# design.net
KiCad netlist of a schematic drawn in Altium Designer
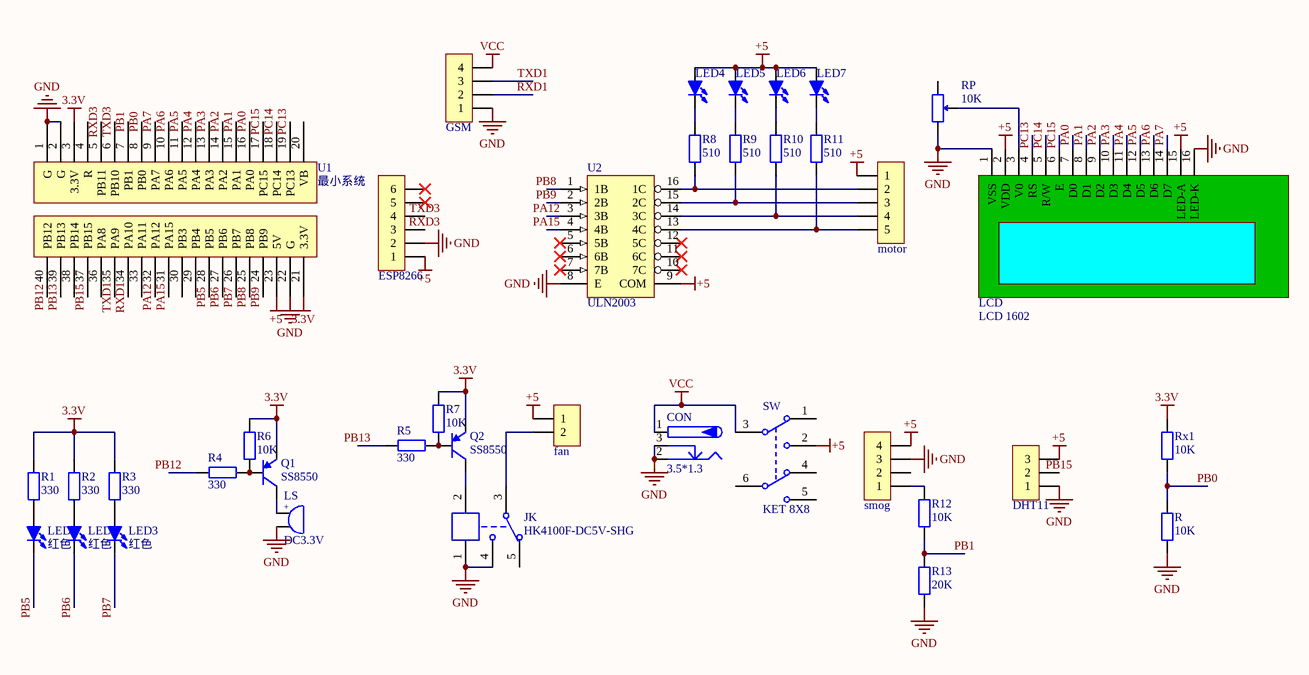
[diagram p0: 原理图.SchDoc]

(export (version "E")
  (design (tool "Eeschema 10.0.6"))
  (components
    (comp (ref "CON")
      (value "3.5*1.3")
      (footprint "DC-005")
      (description "低压电源接口")
      (fields (field (name "版权归属") "源创客"))
      (libsource (lib "4.1   - 接口类") (part "P-DC"))
    )
    (comp (ref "DHT11")
      (value "HDR-1X3")
      (footprint "HDR2.54-M-LI-3P")
      (description "3P接插件")
      (fields (field (name "版权归属") "源创客"))
      (libsource (lib "4.5   - 接插件-脚距2.54") (part "Header 3"))
    )
    (comp (ref "ESP8266")
      (value "HDR-1X6")
      (footprint "HDR2.54-M-LI-6P")
      (description "6P接插件")
      (fields (field (name "版权归属") "源创客"))
      (libsource (lib "4.5   - 接插件-脚距2.54") (part "Header 6"))
    )
    (comp (ref "fan")
      (value "HDR-1X2")
      (footprint "HDR2.54-LI-2P")
      (description "2P接插件")
      (fields (field (name "版权归属") "源创客"))
      (libsource (lib "4.5   - 接插件-脚距2.54") (part "Header 2"))
    )
    (comp (ref "GSM")
      (value "HDR-1X4")
      (footprint "HDR2.54-LI-4P")
      (description "4P接插件")
      (fields (field (name "版权归属") "源创客"))
      (libsource (lib "4.5   - 接插件-脚距2.54") (part "Header 4"))
    )
    (comp (ref "JK")
      (value "HK4100F-DC5V-SHG")
      (footprint "HK4100F")
      (description "一组转换")
      (fields (field (name "版权归属") "源创客"))
      (libsource (lib "7.1   - 继电器") (part "HK4100F"))
    )
    (comp (ref "LCD")
      (value "LCD 1602")
      (footprint "LCD-1602")
      (fields (field (name "版权归属") "源创客"))
      (libsource (lib "9.2   - 显示器件") (part "LCD 1602"))
    )
    (comp (ref "LED1")
      (value "红色")
      (footprint "LED 0805G")
      (description "贴片LED")
      (fields (field (name "版权归属") "源创客"))
      (libsource (lib "9.1   - LED") (part "LED-SMD"))
    )
    (comp (ref "LED2")
      (value "红色")
      (footprint "LED 0805G")
      (description "贴片LED")
      (fields (field (name "版权归属") "源创客"))
      (libsource (lib "9.1   - LED") (part "LED-SMD"))
    )
    (comp (ref "LED3")
      (value "红色")
      (footprint "LED 0805G")
      (description "贴片LED")
      (fields (field (name "版权归属") "源创客"))
      (libsource (lib "9.1   - LED") (part "LED-SMD"))
    )
    (comp (ref "LED4")
      (value "~")
      (footprint "LED 0805G")
      (description "贴片LED")
      (fields (field (name "版权归属") "源创客"))
      (libsource (lib "9.1   - LED") (part "LED-SMD"))
    )
    (comp (ref "LED5")
      (value "~")
      (footprint "LED 0805G")
      (description "贴片LED")
      (fields (field (name "版权归属") "源创客"))
      (libsource (lib "9.1   - LED") (part "LED-SMD"))
    )
    (comp (ref "LED6")
      (value "~")
      (footprint "LED 0805G")
      (description "贴片LED")
      (fields (field (name "版权归属") "源创客"))
      (libsource (lib "9.1   - LED") (part "LED-SMD"))
    )
    (comp (ref "LED7")
      (value "~")
      (footprint "LED 0805G")
      (description "贴片LED")
      (fields (field (name "版权归属") "源创客"))
      (libsource (lib "9.1   - LED") (part "LED-SMD"))
    )
    (comp (ref "LS")
      (value "DC3.3V")
      (footprint "BEEP 5x9x5.5")
      (description "蜂鸣器")
      (fields (field (name "版权归属") "源创客"))
      (libsource (lib "15.1 - 未分类器件") (part "BEEP"))
    )
    (comp (ref "motor")
      (value "HDR-1X5")
      (footprint "XH2.54-LI-5P")
      (description "5P接插件")
      (fields (field (name "版权归属") "源创客"))
      (libsource (lib "4.5   - 接插件-脚距2.54") (part "Header 5"))
    )
    (comp (ref "Q1")
      (value "SS8550")
      (footprint "SOT23-3M")
      (description "高频放大-PNP型")
      (fields (field (name "版权归属") "源创客"))
      (libsource (lib "6.2   - 三极管") (part "8550-SMD"))
    )
    (comp (ref "Q2")
      (value "SS8550")
      (footprint "SOT23-3M")
      (description "高频放大-PNP型")
      (fields (field (name "版权归属") "源创客"))
      (libsource (lib "6.2   - 三极管") (part "8550-SMD"))
    )
    (comp (ref "R")
      (value "10K")
      (footprint "RS 1/4W")
      (description "直插色环电阻")
      (fields (field (name "版权归属") "源创客"))
      (libsource (lib "3.1   - 电阻-电容-电感") (part "R-CRR"))
    )
    (comp (ref "R1")
      (value "330")
      (footprint "R 0805_M")
      (description "贴片电阻")
      (fields (field (name "版权归属") "源创客"))
      (libsource (lib "3.1   - 电阻-电容-电感") (part "R"))
    )
    (comp (ref "R2")
      (value "330")
      (footprint "R 0805_M")
      (description "贴片电阻")
      (fields (field (name "版权归属") "源创客"))
      (libsource (lib "3.1   - 电阻-电容-电感") (part "R"))
    )
    (comp (ref "R3")
      (value "330")
      (footprint "R 0805_M")
      (description "贴片电阻")
      (fields (field (name "版权归属") "源创客"))
      (libsource (lib "3.1   - 电阻-电容-电感") (part "R"))
    )
    (comp (ref "R4")
      (value "330")
      (footprint "R 0805_M")
      (description "贴片电阻")
      (fields (field (name "版权归属") "源创客"))
      (libsource (lib "3.1   - 电阻-电容-电感") (part "R"))
    )
    (comp (ref "R5")
      (value "330")
      (footprint "R 0805_M")
      (description "贴片电阻")
      (fields (field (name "版权归属") "源创客"))
      (libsource (lib "3.1   - 电阻-电容-电感") (part "R"))
    )
    (comp (ref "R6")
      (value "10K")
      (footprint "R 0805_M")
      (description "贴片电阻")
      (fields (field (name "版权归属") "源创客"))
      (libsource (lib "3.1   - 电阻-电容-电感") (part "R"))
    )
    (comp (ref "R7")
      (value "10K")
      (footprint "R 0805_M")
      (description "贴片电阻")
      (fields (field (name "版权归属") "源创客"))
      (libsource (lib "3.1   - 电阻-电容-电感") (part "R"))
    )
    (comp (ref "R8")
      (value "510")
      (footprint "R 0805_M")
      (description "贴片电阻")
      (fields (field (name "版权归属") "源创客"))
      (libsource (lib "3.1   - 电阻-电容-电感") (part "R"))
    )
    (comp (ref "R9")
      (value "510")
      (footprint "R 0805_M")
      (description "贴片电阻")
      (fields (field (name "版权归属") "源创客"))
      (libsource (lib "3.1   - 电阻-电容-电感") (part "R"))
    )
    (comp (ref "R10")
      (value "510")
      (footprint "R 0805_M")
      (description "贴片电阻")
      (fields (field (name "版权归属") "源创客"))
      (libsource (lib "3.1   - 电阻-电容-电感") (part "R"))
    )
    (comp (ref "R11")
      (value "510")
      (footprint "R 0805_M")
      (description "贴片电阻")
      (fields (field (name "版权归属") "源创客"))
      (libsource (lib "3.1   - 电阻-电容-电感") (part "R"))
    )
    (comp (ref "R12")
      (value "10K")
      (footprint "RS 1/4W")
      (description "直插色环电阻")
      (fields (field (name "版权归属") "源创客"))
      (libsource (lib "3.1   - 电阻-电容-电感") (part "R-CRR"))
    )
    (comp (ref "R13")
      (value "20K")
      (footprint "RS 1/4W")
      (description "直插色环电阻")
      (fields (field (name "版权归属") "源创客"))
      (libsource (lib "3.1   - 电阻-电容-电感") (part "R-CRR"))
    )
    (comp (ref "RP")
      (value "10K")
      (footprint "RM065")
      (description "插件单联电位器")
      (fields (field (name "版权归属") "源创客"))
      (libsource (lib "3.1   - 电阻-电容-电感") (part "RP-ID"))
    )
    (comp (ref "Rx1")
      (value "10K")
      (footprint "RS 1/4W")
      (description "直插色环电阻")
      (fields (field (name "版权归属") "源创客"))
      (libsource (lib "3.1   - 电阻-电容-电感") (part "R-CRR"))
    )
    (comp (ref "smog")
      (value "HDR-1X4")
      (footprint "HDR2.54-M-LI-4P")
      (description "4P接插件")
      (fields (field (name "版权归属") "源创客"))
      (libsource (lib "4.5   - 接插件-脚距2.54") (part "Header 4"))
    )
    (comp (ref "SW")
      (value "KET 8X8")
      (footprint "KFT DIP-8X8")
      (description "8*8自锁开关")
      (fields (field (name "版权归属") "源创客"))
      (libsource (lib "5.1   - 按键-开关") (part "KET 8X8"))
    )
    (comp (ref "U1")
      (value "最小系统")
      (footprint "MINI")
      (libsource (lib "STM32F103C8T6最小系统板") (part "c8t6最小系统"))
    )
    (comp (ref "U2")
      (value "ULN2003")
      (footprint "DIP16-300")
      (description "达林顿驱动芯片")
      (fields (field (name "版权归属") "源创客"))
      (libsource (lib "1.1   - IC芯片") (part "ULN2003-2"))
    )
  )
  (nets
    (net (code "1") (name "+5") (class "Default")
      (node (ref "DHT11") (pin "3") (pinfunction "3_3") (pintype "passive"))
      (node (ref "ESP8266") (pin "1") (pinfunction "1_1") (pintype "passive"))
      (node (ref "LCD") (pin "15") (pinfunction "LED-A_15") (pintype "passive"))
      (node (ref "LCD") (pin "2") (pinfunction "VDD_2") (pintype "passive"))
      (node (ref "LED4") (pin "1") (pinfunction "A_1") (pintype "passive"))
      (node (ref "LED5") (pin "1") (pinfunction "A_1") (pintype "passive"))
      (node (ref "LED6") (pin "1") (pinfunction "A_1") (pintype "passive"))
      (node (ref "LED7") (pin "1") (pinfunction "A_1") (pintype "passive"))
      (node (ref "SW") (pin "2") (pinfunction "COM2_2") (pintype "passive"))
      (node (ref "U1") (pin "23") (pinfunction "5V_23") (pintype "passive"))
      (node (ref "U2") (pin "9") (pinfunction "COM_9") (pintype "passive"))
      (node (ref "fan") (pin "1") (pinfunction "1_1") (pintype "passive"))
      (node (ref "motor") (pin "1") (pinfunction "1_1") (pintype "passive"))
      (node (ref "smog") (pin "4") (pinfunction "4_4") (pintype "passive"))
    )
    (net (code "2") (name "/PA0") (class "Default")
      (node (ref "LCD") (pin "7") (pinfunction "D0_7") (pintype "passive"))
      (node (ref "U1") (pin "16") (pinfunction "PA0_16") (pintype "passive"))
    )
    (net (code "3") (name "/PA1") (class "Default")
      (node (ref "LCD") (pin "8") (pinfunction "D1_8") (pintype "passive"))
      (node (ref "U1") (pin "15") (pinfunction "PA1_15") (pintype "passive"))
    )
    (net (code "4") (name "/PA2") (class "Default")
      (node (ref "LCD") (pin "9") (pinfunction "D2_9") (pintype "passive"))
      (node (ref "U1") (pin "14") (pinfunction "PA2_14") (pintype "passive"))
    )
    (net (code "5") (name "/PA3") (class "Default")
      (node (ref "LCD") (pin "10") (pinfunction "D3_10") (pintype "passive"))
      (node (ref "U1") (pin "13") (pinfunction "PA3_13") (pintype "passive"))
    )
    (net (code "6") (name "/PA4") (class "Default")
      (node (ref "LCD") (pin "11") (pinfunction "D4_11") (pintype "passive"))
      (node (ref "U1") (pin "12") (pinfunction "PA4_12") (pintype "passive"))
    )
    (net (code "7") (name "/PA5") (class "Default")
      (node (ref "LCD") (pin "12") (pinfunction "D5_12") (pintype "passive"))
      (node (ref "U1") (pin "11") (pinfunction "PA5_11") (pintype "passive"))
    )
    (net (code "8") (name "/PA6") (class "Default")
      (node (ref "LCD") (pin "13") (pinfunction "D6_13") (pintype "passive"))
      (node (ref "U1") (pin "10") (pinfunction "PA6_10") (pintype "passive"))
    )
    (net (code "9") (name "/PA7") (class "Default")
      (node (ref "LCD") (pin "14") (pinfunction "D7_14") (pintype "passive"))
      (node (ref "U1") (pin "9") (pinfunction "PA7_9") (pintype "passive"))
    )
    (net (code "10") (name "/PA12") (class "Default")
      (node (ref "U1") (pin "32") (pinfunction "PA12_32") (pintype "passive"))
      (node (ref "U2") (pin "3") (pinfunction "3B_3") (pintype "input"))
    )
    (net (code "11") (name "/PA15") (class "Default")
      (node (ref "U1") (pin "31") (pinfunction "PA15_31") (pintype "passive"))
      (node (ref "U2") (pin "4") (pinfunction "4B_4") (pintype "input"))
    )
    (net (code "12") (name "/PB0") (class "Default")
      (node (ref "R") (pin "2") (pinfunction "2_2") (pintype "passive"))
      (node (ref "Rx1") (pin "1") (pinfunction "1_1") (pintype "passive"))
      (node (ref "U1") (pin "8") (pinfunction "PB0_8") (pintype "passive"))
    )
    (net (code "13") (name "/PB1") (class "Default")
      (node (ref "R12") (pin "1") (pinfunction "1_1") (pintype "passive"))
      (node (ref "R13") (pin "2") (pinfunction "2_2") (pintype "passive"))
      (node (ref "U1") (pin "7") (pinfunction "PB1_7") (pintype "passive"))
    )
    (net (code "14") (name "/PB5") (class "Default")
      (node (ref "LED1") (pin "2") (pinfunction "K_2") (pintype "passive"))
      (node (ref "U1") (pin "28") (pinfunction "PB5_28") (pintype "passive"))
    )
    (net (code "15") (name "/PB6") (class "Default")
      (node (ref "LED2") (pin "2") (pinfunction "K_2") (pintype "passive"))
      (node (ref "U1") (pin "27") (pinfunction "PB6_27") (pintype "passive"))
    )
    (net (code "16") (name "/PB7") (class "Default")
      (node (ref "LED3") (pin "2") (pinfunction "K_2") (pintype "passive"))
      (node (ref "U1") (pin "26") (pinfunction "PB7_26") (pintype "passive"))
    )
    (net (code "17") (name "/PB8") (class "Default")
      (node (ref "U1") (pin "25") (pinfunction "PB8_25") (pintype "passive"))
      (node (ref "U2") (pin "1") (pinfunction "1B_1") (pintype "input"))
    )
    (net (code "18") (name "/PB9") (class "Default")
      (node (ref "U1") (pin "24") (pinfunction "PB9_24") (pintype "passive"))
      (node (ref "U2") (pin "2") (pinfunction "2B_2") (pintype "input"))
    )
    (net (code "19") (name "/PB12") (class "Default")
      (node (ref "R4") (pin "1") (pinfunction "1_1") (pintype "passive"))
      (node (ref "U1") (pin "40") (pinfunction "PB12_40") (pintype "passive"))
    )
    (net (code "20") (name "/PB13") (class "Default")
      (node (ref "R5") (pin "1") (pinfunction "1_1") (pintype "passive"))
      (node (ref "U1") (pin "39") (pinfunction "PB13_39") (pintype "passive"))
    )
    (net (code "21") (name "/PB15") (class "Default")
      (node (ref "DHT11") (pin "2") (pinfunction "2_2") (pintype "passive"))
      (node (ref "U1") (pin "37") (pinfunction "PB15_37") (pintype "passive"))
    )
    (net (code "22") (name "/PC13") (class "Default")
      (node (ref "LCD") (pin "4") (pinfunction "RS_4") (pintype "passive"))
      (node (ref "U1") (pin "19") (pinfunction "PC13_19") (pintype "passive"))
    )
    (net (code "23") (name "/PC14") (class "Default")
      (node (ref "LCD") (pin "5") (pinfunction "R/W_5") (pintype "passive"))
      (node (ref "U1") (pin "18") (pinfunction "PC14_18") (pintype "passive"))
    )
    (net (code "24") (name "/PC15") (class "Default")
      (node (ref "LCD") (pin "6") (pinfunction "E_6") (pintype "passive"))
      (node (ref "U1") (pin "17") (pinfunction "PC15_17") (pintype "passive"))
    )
    (net (code "25") (name "/RXD1") (class "Default")
      (node (ref "GSM") (pin "2") (pinfunction "2_2") (pintype "passive"))
      (node (ref "U1") (pin "34") (pinfunction "PA10_34") (pintype "passive"))
    )
    (net (code "26") (name "/RXD3") (class "Default")
      (node (ref "ESP8266") (pin "3") (pinfunction "3_3") (pintype "passive"))
      (node (ref "U1") (pin "5") (pinfunction "PB11_5") (pintype "passive"))
    )
    (net (code "27") (name "/TXD1") (class "Default")
      (node (ref "GSM") (pin "3") (pinfunction "3_3") (pintype "passive"))
      (node (ref "U1") (pin "35") (pinfunction "PA9_35") (pintype "passive"))
    )
    (net (code "28") (name "/TXD3") (class "Default")
      (node (ref "ESP8266") (pin "4") (pinfunction "4_4") (pintype "passive"))
      (node (ref "U1") (pin "6") (pinfunction "PB10_6") (pintype "passive"))
    )
    (net (code "29") (name "3.3V") (class "Default")
      (node (ref "Q1") (pin "2") (pinfunction "E_2") (pintype "passive"))
      (node (ref "Q2") (pin "2") (pinfunction "E_2") (pintype "passive"))
      (node (ref "R1") (pin "2") (pinfunction "2_2") (pintype "passive"))
      (node (ref "R2") (pin "2") (pinfunction "2_2") (pintype "passive"))
      (node (ref "R3") (pin "2") (pinfunction "2_2") (pintype "passive"))
      (node (ref "R6") (pin "2") (pinfunction "2_2") (pintype "passive"))
      (node (ref "R7") (pin "2") (pinfunction "2_2") (pintype "passive"))
      (node (ref "Rx1") (pin "2") (pinfunction "2_2") (pintype "passive"))
      (node (ref "U1") (pin "21") (pinfunction "3.3V_21") (pintype "passive"))
      (node (ref "U1") (pin "3") (pinfunction "3.3V_3") (pintype "passive"))
    )
    (net (code "30") (name "GND") (class "Default")
      (node (ref "CON") (pin "2") (pintype "power_in"))
      (node (ref "CON") (pin "3") (pintype "power_in"))
      (node (ref "DHT11") (pin "1") (pinfunction "1_1") (pintype "passive"))
      (node (ref "ESP8266") (pin "2") (pinfunction "2_2") (pintype "passive"))
      (node (ref "GSM") (pin "1") (pinfunction "1_1") (pintype "passive"))
      (node (ref "JK") (pin "1") (pinfunction "1_1") (pintype "passive"))
      (node (ref "JK") (pin "4") (pinfunction "4_4") (pintype "passive"))
      (node (ref "LCD") (pin "1") (pinfunction "VSS_1") (pintype "passive"))
      (node (ref "LCD") (pin "16") (pinfunction "LED-K_16") (pintype "passive"))
      (node (ref "LS") (pin "2") (pinfunction "2_2") (pintype "passive"))
      (node (ref "R") (pin "1") (pinfunction "1_1") (pintype "passive"))
      (node (ref "R13") (pin "1") (pinfunction "1_1") (pintype "passive"))
      (node (ref "RP") (pin "3") (pinfunction "3_3") (pintype "passive"))
      (node (ref "U1") (pin "1") (pinfunction "G_1") (pintype "passive"))
      (node (ref "U1") (pin "2") (pinfunction "G_2") (pintype "passive"))
      (node (ref "U1") (pin "22") (pinfunction "G_22") (pintype "passive"))
      (node (ref "U2") (pin "8") (pinfunction "E_8") (pintype "passive"))
      (node (ref "smog") (pin "3") (pinfunction "3_3") (pintype "passive"))
    )
    (net (code "31") (name "Net-(JK-Pad3)") (class "Default")
      (node (ref "JK") (pin "3") (pinfunction "3_3") (pintype "passive"))
      (node (ref "fan") (pin "2") (pinfunction "2_2") (pintype "passive"))
    )
    (net (code "32") (name "Net-(LCD-V0)") (class "Default")
      (node (ref "LCD") (pin "3") (pinfunction "V0_3") (pintype "passive"))
      (node (ref "RP") (pin "2") (pinfunction "2_2") (pintype "passive"))
    )
    (net (code "33") (name "Net-(LED1-A)") (class "Default")
      (node (ref "LED1") (pin "1") (pinfunction "A_1") (pintype "passive"))
      (node (ref "R1") (pin "1") (pinfunction "1_1") (pintype "passive"))
    )
    (net (code "34") (name "Net-(LED2-A)") (class "Default")
      (node (ref "LED2") (pin "1") (pinfunction "A_1") (pintype "passive"))
      (node (ref "R2") (pin "1") (pinfunction "1_1") (pintype "passive"))
    )
    (net (code "35") (name "Net-(LED3-A)") (class "Default")
      (node (ref "LED3") (pin "1") (pinfunction "A_1") (pintype "passive"))
      (node (ref "R3") (pin "1") (pinfunction "1_1") (pintype "passive"))
    )
    (net (code "36") (name "Net-(LED4-K)") (class "Default")
      (node (ref "LED4") (pin "2") (pinfunction "K_2") (pintype "passive"))
      (node (ref "R8") (pin "2") (pinfunction "2_2") (pintype "passive"))
    )
    (net (code "37") (name "Net-(LED5-K)") (class "Default")
      (node (ref "LED5") (pin "2") (pinfunction "K_2") (pintype "passive"))
      (node (ref "R9") (pin "2") (pinfunction "2_2") (pintype "passive"))
    )
    (net (code "38") (name "Net-(LED6-K)") (class "Default")
      (node (ref "LED6") (pin "2") (pinfunction "K_2") (pintype "passive"))
      (node (ref "R10") (pin "2") (pinfunction "2_2") (pintype "passive"))
    )
    (net (code "39") (name "Net-(LED7-K)") (class "Default")
      (node (ref "LED7") (pin "2") (pinfunction "K_2") (pintype "passive"))
      (node (ref "R11") (pin "2") (pinfunction "2_2") (pintype "passive"))
    )
    (net (code "40") (name "Net-(Q1-B)") (class "Default")
      (node (ref "Q1") (pin "1") (pinfunction "B_1") (pintype "passive"))
      (node (ref "R4") (pin "2") (pinfunction "2_2") (pintype "passive"))
      (node (ref "R6") (pin "1") (pinfunction "1_1") (pintype "passive"))
    )
    (net (code "41") (name "Net-(Q1-C)") (class "Default")
      (node (ref "LS") (pin "1") (pinfunction "1_1") (pintype "passive"))
      (node (ref "Q1") (pin "3") (pinfunction "C_3") (pintype "passive"))
    )
    (net (code "42") (name "Net-(Q2-B)") (class "Default")
      (node (ref "Q2") (pin "1") (pinfunction "B_1") (pintype "passive"))
      (node (ref "R5") (pin "2") (pinfunction "2_2") (pintype "passive"))
      (node (ref "R7") (pin "1") (pinfunction "1_1") (pintype "passive"))
    )
    (net (code "43") (name "Net-(Q2-C)") (class "Default")
      (node (ref "JK") (pin "2") (pinfunction "2_2") (pintype "passive"))
      (node (ref "Q2") (pin "3") (pinfunction "C_3") (pintype "passive"))
    )
    (net (code "44") (name "Net-(R12-Pad2)") (class "Default")
      (node (ref "R12") (pin "2") (pinfunction "2_2") (pintype "passive"))
      (node (ref "smog") (pin "1") (pinfunction "1_1") (pintype "passive"))
    )
    (net (code "45") (name "Net-(U2-1C)") (class "Default")
      (node (ref "R8") (pin "1") (pinfunction "1_1") (pintype "passive"))
      (node (ref "U2") (pin "16") (pinfunction "1C_16") (pintype "open_collector"))
      (node (ref "motor") (pin "2") (pinfunction "2_2") (pintype "passive"))
    )
    (net (code "46") (name "Net-(U2-2C)") (class "Default")
      (node (ref "R9") (pin "1") (pinfunction "1_1") (pintype "passive"))
      (node (ref "U2") (pin "15") (pinfunction "2C_15") (pintype "open_collector"))
      (node (ref "motor") (pin "3") (pinfunction "3_3") (pintype "passive"))
    )
    (net (code "47") (name "Net-(U2-3C)") (class "Default")
      (node (ref "R10") (pin "1") (pinfunction "1_1") (pintype "passive"))
      (node (ref "U2") (pin "14") (pinfunction "3C_14") (pintype "open_collector"))
      (node (ref "motor") (pin "4") (pinfunction "4_4") (pintype "passive"))
    )
    (net (code "48") (name "Net-(U2-4C)") (class "Default")
      (node (ref "R11") (pin "1") (pinfunction "1_1") (pintype "passive"))
      (node (ref "U2") (pin "13") (pinfunction "4C_13") (pintype "open_collector"))
      (node (ref "motor") (pin "5") (pinfunction "5_5") (pintype "passive"))
    )
    (net (code "49") (name "VCC") (class "Default")
      (node (ref "CON") (pin "1") (pintype "power_in"))
      (node (ref "GSM") (pin "4") (pinfunction "4_4") (pintype "passive"))
      (node (ref "SW") (pin "3") (pinfunction "NO1_3") (pintype "passive"))
    )
    (net (code "50") (name "unconnected-(ESP8266-Pad5)") (class "Default")
      (node (ref "ESP8266") (pin "5") (pinfunction "5_5") (pintype "passive+no_connect"))
    )
    (net (code "51") (name "unconnected-(ESP8266-Pad6)") (class "Default")
      (node (ref "ESP8266") (pin "6") (pinfunction "6_6") (pintype "passive+no_connect"))
    )
    (net (code "52") (name "unconnected-(JK-Pad5)") (class "Default")
      (node (ref "JK") (pin "5") (pinfunction "5_5") (pintype "passive"))
    )
    (net (code "53") (name "unconnected-(RP-Pad1)") (class "Default")
      (node (ref "RP") (pin "1") (pinfunction "1_1") (pintype "passive"))
    )
    (net (code "54") (name "unconnected-(SW-COM2-Pad5)") (class "Default")
      (node (ref "SW") (pin "5") (pinfunction "COM2_5") (pintype "passive"))
    )
    (net (code "55") (name "unconnected-(SW-NC1-Pad1)") (class "Default")
      (node (ref "SW") (pin "1") (pinfunction "NC1_1") (pintype "passive"))
    )
    (net (code "56") (name "unconnected-(SW-NC2-Pad6)") (class "Default")
      (node (ref "SW") (pin "6") (pinfunction "NC2_6") (pintype "passive"))
    )
    (net (code "57") (name "unconnected-(SW-NO2-Pad4)") (class "Default")
      (node (ref "SW") (pin "4") (pinfunction "NO2_4") (pintype "passive"))
    )
    (net (code "58") (name "unconnected-(U1-PA8-Pad36)") (class "Default")
      (node (ref "U1") (pin "36") (pinfunction "PA8_36") (pintype "passive"))
    )
    (net (code "59") (name "unconnected-(U1-PA11-Pad33)") (class "Default")
      (node (ref "U1") (pin "33") (pinfunction "PA11_33") (pintype "passive"))
    )
    (net (code "60") (name "unconnected-(U1-PB3-Pad30)") (class "Default")
      (node (ref "U1") (pin "30") (pinfunction "PB3_30") (pintype "passive"))
    )
    (net (code "61") (name "unconnected-(U1-PB4-Pad29)") (class "Default")
      (node (ref "U1") (pin "29") (pinfunction "PB4_29") (pintype "passive"))
    )
    (net (code "62") (name "unconnected-(U1-PB14-Pad38)") (class "Default")
      (node (ref "U1") (pin "38") (pinfunction "PB14_38") (pintype "passive"))
    )
    (net (code "63") (name "unconnected-(U1-R-Pad4)") (class "Default")
      (node (ref "U1") (pin "4") (pinfunction "R_4") (pintype "passive"))
    )
    (net (code "64") (name "unconnected-(U1-VB-Pad20)") (class "Default")
      (node (ref "U1") (pin "20") (pinfunction "VB_20") (pintype "passive"))
    )
    (net (code "65") (name "unconnected-(U2-5B-Pad5)") (class "Default")
      (node (ref "U2") (pin "5") (pinfunction "5B_5") (pintype "input+no_connect"))
    )
    (net (code "66") (name "unconnected-(U2-5C-Pad12)") (class "Default")
      (node (ref "U2") (pin "12") (pinfunction "5C_12") (pintype "open_collector+no_connect"))
    )
    (net (code "67") (name "unconnected-(U2-6B-Pad6)") (class "Default")
      (node (ref "U2") (pin "6") (pinfunction "6B_6") (pintype "input+no_connect"))
    )
    (net (code "68") (name "unconnected-(U2-6C-Pad11)") (class "Default")
      (node (ref "U2") (pin "11") (pinfunction "6C_11") (pintype "open_collector+no_connect"))
    )
    (net (code "69") (name "unconnected-(U2-7B-Pad7)") (class "Default")
      (node (ref "U2") (pin "7") (pinfunction "7B_7") (pintype "input+no_connect"))
    )
    (net (code "70") (name "unconnected-(U2-7C-Pad10)") (class "Default")
      (node (ref "U2") (pin "10") (pinfunction "7C_10") (pintype "open_collector+no_connect"))
    )
    (net (code "71") (name "unconnected-(smog-Pad2)") (class "Default")
      (node (ref "smog") (pin "2") (pinfunction "2_2") (pintype "passive"))
    )
  )
)
